# MP135_11x11.net
KiCad netlist of a schematic drawn in Altium Designer
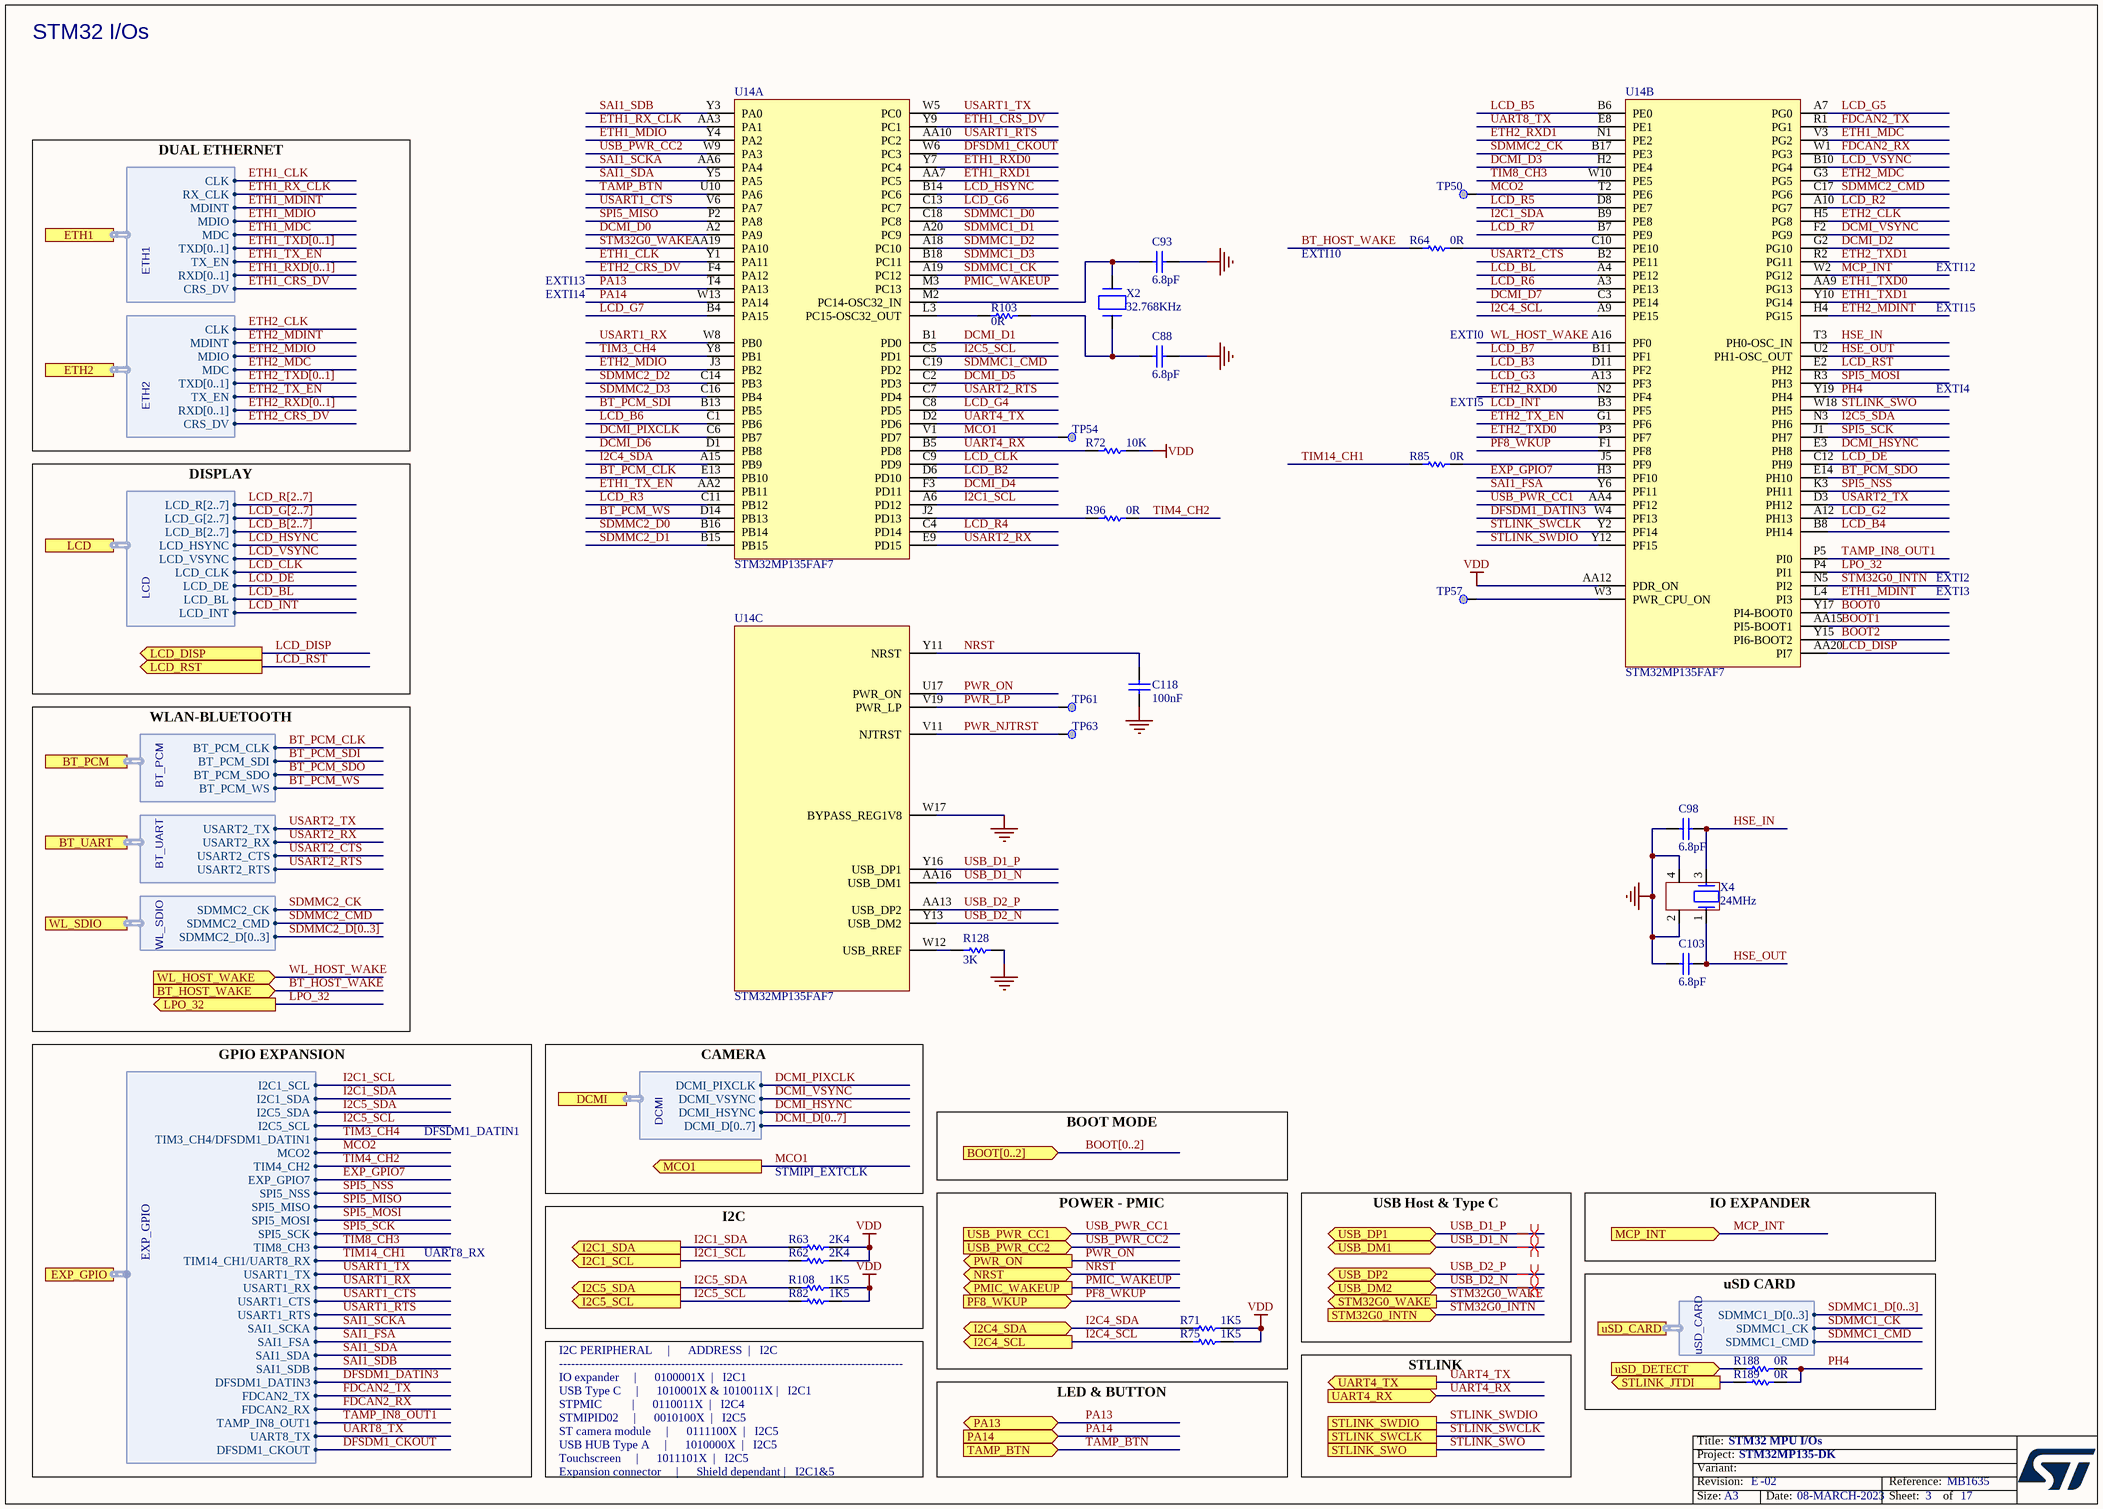
[diagram p0: MP135_11x11.SchDoc]

(export (version "E")
  (design (tool "Eeschema 10.0.6"))
  (components
    (comp (ref "C88")
      (value "6.8pF")
      (footprint "C0402")
      (description "Capacitor, MLCC, 6.8pF, 50V, NPO, +/-0.25pF, 0402, T=0.5mm")
      (fields
        (field (name "INTERNAL_PART_NUMBER") "MCD-00674")
        (field (name "MANUFACTURER_PART_NUMBER") "CC0402CRNPO9BN6R8")
      )
      (libsource (lib "MCD_PARTS_database") (part "Capacitor"))
    )
    (comp (ref "C93")
      (value "6.8pF")
      (footprint "C0402")
      (description "Capacitor, MLCC, 6.8pF, 50V, NPO, +/-0.25pF, 0402, T=0.5mm")
      (fields
        (field (name "INTERNAL_PART_NUMBER") "MCD-00674")
        (field (name "MANUFACTURER_PART_NUMBER") "CC0402CRNPO9BN6R8")
      )
      (libsource (lib "MCD_PARTS_database") (part "Capacitor"))
    )
    (comp (ref "C98")
      (value "6.8pF")
      (footprint "C0402")
      (description "Capacitor, MLCC, 6.8pF, 50V, NPO, +/-0.25pF, 0402, T=0.5mm")
      (fields
        (field (name "INTERNAL_PART_NUMBER") "MCD-00674")
        (field (name "MANUFACTURER_PART_NUMBER") "CC0402CRNPO9BN6R8")
      )
      (libsource (lib "MCD_PARTS_database") (part "Capacitor"))
    )
    (comp (ref "C103")
      (value "6.8pF")
      (footprint "C0402")
      (description "Capacitor, MLCC, 6.8pF, 50V, NPO, +/-0.25pF, 0402, T=0.5mm")
      (fields
        (field (name "INTERNAL_PART_NUMBER") "MCD-00674")
        (field (name "MANUFACTURER_PART_NUMBER") "CC0402CRNPO9BN6R8")
      )
      (libsource (lib "MCD_PARTS_database") (part "Capacitor"))
    )
    (comp (ref "C118")
      (value "100nF")
      (footprint "C0402")
      (description "Capacitor, MLCC, 100nF, 16V, X7R, +/-10%, 0402, T=0.5mm")
      (fields
        (field (name "INTERNAL_PART_NUMBER") "MCD-00006")
        (field (name "MANUFACTURER_PART_NUMBER") "CC0402KRX7R7BB104")
      )
      (libsource (lib "MCD_PARTS_database") (part "Capacitor"))
    )
    (comp (ref "R62")
      (value "2K4")
      (footprint "R0402")
      (description "Resistor, 2K4, 0402, +/-1%, 1/16W")
      (fields (field (name "INTERNAL_PART_NUMBER") "MCD-00433") (field (name "MANUFACTURER") "YAGEO"))
      (libsource (lib "MCD_PARTS_database") (part "Resistor"))
    )
    (comp (ref "R63")
      (value "2K4")
      (footprint "R0402")
      (description "Resistor, 2K4, 0402, +/-1%, 1/16W")
      (fields (field (name "INTERNAL_PART_NUMBER") "MCD-00433") (field (name "MANUFACTURER") "YAGEO"))
      (libsource (lib "MCD_PARTS_database") (part "Resistor"))
    )
    (comp (ref "R64")
      (value "0R")
      (footprint "R0402")
      (description "Resistor, 0R, 0402, +/-5%, 1/16W")
      (fields (field (name "INTERNAL_PART_NUMBER") "MCD-00052") (field (name "MANUFACTURER") "YAGEO"))
      (libsource (lib "MCD_PARTS_database") (part "Resistor"))
    )
    (comp (ref "R71")
      (value "1K5")
      (footprint "R0402")
      (description "Resistor, 1K5, 0402, +/-1%, 1/16W")
      (fields (field (name "INTERNAL_PART_NUMBER") "MCD-00068") (field (name "MANUFACTURER") "YAGEO"))
      (libsource (lib "MCD_PARTS_database") (part "Resistor"))
    )
    (comp (ref "R72")
      (value "10K")
      (footprint "R0402")
      (description "Resistor, 10K, 0402, +/-1%, 1/16W")
      (fields
        (field (name "INTERNAL_PART_NUMBER") "MCD-00053")
        (field (name "MANUFACTURER_PART_NUMBER") "RC0402FR-0710KL")
      )
      (libsource (lib "MCD_PARTS_database") (part "Resistor"))
    )
    (comp (ref "R75")
      (value "1K5")
      (footprint "R0402")
      (description "Resistor, 1K5, 0402, +/-1%, 1/16W")
      (fields (field (name "INTERNAL_PART_NUMBER") "MCD-00068") (field (name "MANUFACTURER") "YAGEO"))
      (libsource (lib "MCD_PARTS_database") (part "Resistor"))
    )
    (comp (ref "R82")
      (value "1K5")
      (footprint "R0402")
      (description "Resistor, 1K5, 0402, +/-1%, 1/16W")
      (fields (field (name "INTERNAL_PART_NUMBER") "MCD-00068") (field (name "MANUFACTURER") "YAGEO"))
      (libsource (lib "MCD_PARTS_database") (part "Resistor"))
    )
    (comp (ref "R85")
      (value "0R")
      (footprint "R0402")
      (description "Resistor, 0R, 0402, +/-5%, 1/16W")
      (fields (field (name "INTERNAL_PART_NUMBER") "MCD-00052") (field (name "MANUFACTURER") "YAGEO"))
      (libsource (lib "MCD_PARTS_database") (part "Resistor"))
    )
    (comp (ref "R96")
      (value "0R")
      (footprint "R0402")
      (description "Resistor, 0R, 0402, +/-5%, 1/16W")
      (fields (field (name "INTERNAL_PART_NUMBER") "MCD-00052") (field (name "MANUFACTURER") "YAGEO"))
      (libsource (lib "MCD_PARTS_database") (part "Resistor"))
    )
    (comp (ref "R103")
      (value "0R")
      (footprint "R0402")
      (description "Resistor, 0R, 0402, +/-5%, 1/16W")
      (fields
        (field (name "INTERNAL_PART_NUMBER") "MCD-00052")
        (field (name "MANUFACTURER_PART_NUMBER") "RC0402JR-070RL")
      )
      (libsource (lib "MCD_PARTS_database") (part "Resistor"))
    )
    (comp (ref "R108")
      (value "1K5")
      (footprint "R0402")
      (description "Resistor, 1K5, 0402, +/-1%, 1/16W")
      (fields (field (name "INTERNAL_PART_NUMBER") "MCD-00068") (field (name "MANUFACTURER") "YAGEO"))
      (libsource (lib "MCD_PARTS_database") (part "Resistor"))
    )
    (comp (ref "R128")
      (value "3K")
      (footprint "R0402")
      (description "Resistor, 3K, 0402, +/-1%, 1/16W")
      (fields (field (name "INTERNAL_PART_NUMBER") "MCD-00185") (field (name "MANUFACTURER") "YAGEO"))
      (libsource (lib "MCD_PARTS_database") (part "Resistor"))
    )
    (comp (ref "R188")
      (value "0R")
      (footprint "R0402")
      (description "Resistor, 0R, 0402, +/-5%, 1/16W")
      (fields (field (name "INTERNAL_PART_NUMBER") "MCD-00052") (field (name "MANUFACTURER") "YAGEO"))
      (libsource (lib "MCD_PARTS_database") (part "Resistor"))
    )
    (comp (ref "R189")
      (value "0R")
      (footprint "R0402")
      (description "Resistor, 0R, 0402, +/-5%, 1/16W")
      (fields (field (name "INTERNAL_PART_NUMBER") "MCD-00052") (field (name "MANUFACTURER") "YAGEO"))
      (libsource (lib "MCD_PARTS_database") (part "Resistor"))
    )
    (comp (ref "TP50")
      (value "Test Point")
      (footprint "TP_SMD_1MM")
      (description "Test Point 1mm")
      (fields (field (name "INTERNAL_PART_NUMBER") "MCD-00074"))
      (libsource (lib "") (part "Test Point_1"))
    )
    (comp (ref "TP54")
      (value "Test Point")
      (footprint "TP_SMD_1MM")
      (description "Test Point 1mm")
      (fields (field (name "INTERNAL_PART_NUMBER") "MCD-00074"))
      (libsource (lib "MCD_PARTS_database") (part "Test Point"))
    )
    (comp (ref "TP57")
      (value "Test Point")
      (footprint "TP_SMD_1MM")
      (description "Test Point 1mm")
      (fields (field (name "INTERNAL_PART_NUMBER") "MCD-00074"))
      (libsource (lib "") (part "Test Point_1"))
    )
    (comp (ref "TP61")
      (value "Test Point")
      (footprint "TP_SMD_1MM")
      (description "Test Point 1mm")
      (fields (field (name "INTERNAL_PART_NUMBER") "MCD-00074"))
      (libsource (lib "MCD_PARTS_database") (part "Test Point"))
    )
    (comp (ref "TP63")
      (value "Test Point")
      (footprint "TP_SMD_1MM")
      (description "Test Point 1mm")
      (fields (field (name "INTERNAL_PART_NUMBER") "MCD-00074"))
      (libsource (lib "MCD_PARTS_database") (part "Test Point"))
    )
    (comp (ref "U14")
      (value "STM32MP135FAF7")
      (footprint "ICC_TFBGA320_11X11_STM32MP135FA7_P050_H1P20")
      (fields
        (field (name "INTERNAL_PART_NUMBER") "MCD-02251")
        (field (name "MANUFACTURER") "STMICROELECTRONICS")
      )
      (libsource (lib "MCD_PARTS_database") (part "STM32MP135FAF7"))
    )
    (comp (ref "X2")
      (value "32.768KHz")
      (footprint "CRY_NX2012SA_2P")
      (description "Crystal, 32.768kHz, 6pF, +/-20ppm, 80K, 2.05x1.2mm")
      (fields
        (field (name "INTERNAL_PART_NUMBER") "MCD-01479")
        (field (name "MANUFACTURER_PART_NUMBER") "NX2012SA-32.768KHZ-EXS00A-MU00527")
      )
      (libsource (lib "MCD_PARTS_database") (part "XTAL_2_PINS"))
    )
    (comp (ref "X4")
      (value "24MHz")
      (footprint "CRY_NX2016SA_4P")
      (description "Crystal, 24MHz, 6pF, +/-20ppm, 80R, 2x1.6mm")
      (fields (field (name "INTERNAL_PART_NUMBER") "MCD-01036") (field (name "BMS_PART_NUMBER") "9157045"))
      (libsource (lib "MCD_PARTS_database") (part "XTAL_4_PINS"))
    )
  )
  (nets
    (net (code "10") (name "/BOOT0") (class "Default")
      (node (ref "U14") (pin "Y17") (pinfunction "PI4-BOOT0_Y17") (pintype "passive"))
    )
    (net (code "11") (name "/BOOT1") (class "Default")
      (node (ref "U14") (pin "AA15") (pinfunction "PI5-BOOT1_AA15") (pintype "passive"))
    )
    (net (code "12") (name "/BOOT2") (class "Default")
      (node (ref "U14") (pin "Y15") (pinfunction "PI6-BOOT2_Y15") (pintype "passive"))
    )
    (net (code "14") (name "/BT_HOST_WAKE") (class "Default")
      (node (ref "R64") (pin "1") (pinfunction "1_1") (pintype "passive"))
    )
    (net (code "15") (name "/BT_PCM_CLK") (class "Default")
      (node (ref "U14") (pin "E13") (pinfunction "PB10_E13") (pintype "passive"))
    )
    (net (code "16") (name "/BT_PCM_SDI") (class "Default")
      (node (ref "U14") (pin "B13") (pinfunction "PB5_B13") (pintype "passive"))
    )
    (net (code "17") (name "/BT_PCM_SDO") (class "Default")
      (node (ref "U14") (pin "E14") (pinfunction "PH10_E14") (pintype "passive"))
    )
    (net (code "18") (name "/BT_PCM_WS") (class "Default")
      (node (ref "U14") (pin "D14") (pinfunction "PB13_D14") (pintype "passive"))
    )
    (net (code "19") (name "/DCMI_D0") (class "Default")
      (node (ref "U14") (pin "A2") (pinfunction "PA9_A2") (pintype "passive"))
    )
    (net (code "20") (name "/DCMI_D1") (class "Default")
      (node (ref "U14") (pin "B1") (pinfunction "PD0_B1") (pintype "passive"))
    )
    (net (code "21") (name "/DCMI_D2") (class "Default")
      (node (ref "U14") (pin "G2") (pinfunction "PG10_G2") (pintype "passive"))
    )
    (net (code "22") (name "/DCMI_D3") (class "Default")
      (node (ref "U14") (pin "H2") (pinfunction "PE4_H2") (pintype "passive"))
    )
    (net (code "23") (name "/DCMI_D4") (class "Default")
      (node (ref "U14") (pin "F3") (pinfunction "PD11_F3") (pintype "passive"))
    )
    (net (code "24") (name "/DCMI_D5") (class "Default")
      (node (ref "U14") (pin "C2") (pinfunction "PD3_C2") (pintype "passive"))
    )
    (net (code "25") (name "/DCMI_D6") (class "Default")
      (node (ref "U14") (pin "D1") (pinfunction "PB8_D1") (pintype "passive"))
    )
    (net (code "26") (name "/DCMI_D7") (class "Default")
      (node (ref "U14") (pin "C3") (pinfunction "PE14_C3") (pintype "passive"))
    )
    (net (code "27") (name "/DCMI_HSYNC") (class "Default")
      (node (ref "U14") (pin "E3") (pinfunction "PH8_E3") (pintype "passive"))
    )
    (net (code "28") (name "/DCMI_PIXCLK") (class "Default")
      (node (ref "U14") (pin "C6") (pinfunction "PB7_C6") (pintype "passive"))
    )
    (net (code "29") (name "/DCMI_VSYNC") (class "Default")
      (node (ref "U14") (pin "F2") (pinfunction "PG9_F2") (pintype "passive"))
    )
    (net (code "31") (name "/DFSDM1_CKOUT") (class "Default")
      (node (ref "U14") (pin "W6") (pinfunction "PC3_W6") (pintype "passive"))
    )
    (net (code "32") (name "/DFSDM1_DATIN3") (class "Default")
      (node (ref "U14") (pin "W4") (pinfunction "PF13_W4") (pintype "passive"))
    )
    (net (code "33") (name "/ETH1_CLK") (class "Default")
      (node (ref "U14") (pin "Y1") (pinfunction "PA11_Y1") (pintype "passive"))
    )
    (net (code "34") (name "/ETH1_CRS_DV") (class "Default")
      (node (ref "U14") (pin "Y9") (pinfunction "PC1_Y9") (pintype "passive"))
    )
    (net (code "35") (name "/ETH1_MDC") (class "Default")
      (node (ref "U14") (pin "V3") (pinfunction "PG2_V3") (pintype "passive"))
    )
    (net (code "36") (name "/ETH1_MDINT") (class "Default")
      (node (ref "U14") (pin "L4") (pinfunction "PI3_L4") (pintype "passive"))
    )
    (net (code "37") (name "/ETH1_MDIO") (class "Default")
      (node (ref "U14") (pin "Y4") (pinfunction "PA2_Y4") (pintype "passive"))
    )
    (net (code "38") (name "/ETH1_RXD0") (class "Default")
      (node (ref "U14") (pin "Y7") (pinfunction "PC4_Y7") (pintype "passive"))
    )
    (net (code "39") (name "/ETH1_RXD1") (class "Default")
      (node (ref "U14") (pin "AA7") (pinfunction "PC5_AA7") (pintype "passive"))
    )
    (net (code "40") (name "/ETH1_RX_CLK") (class "Default")
      (node (ref "U14") (pin "AA3") (pinfunction "PA1_AA3") (pintype "passive"))
    )
    (net (code "41") (name "/ETH1_TXD0") (class "Default")
      (node (ref "U14") (pin "AA9") (pinfunction "PG13_AA9") (pintype "passive"))
    )
    (net (code "42") (name "/ETH1_TXD1") (class "Default")
      (node (ref "U14") (pin "Y10") (pinfunction "PG14_Y10") (pintype "passive"))
    )
    (net (code "44") (name "/ETH1_TX_EN") (class "Default")
      (node (ref "U14") (pin "AA2") (pinfunction "PB11_AA2") (pintype "passive"))
    )
    (net (code "46") (name "/ETH2_CLK") (class "Default")
      (node (ref "U14") (pin "H5") (pinfunction "PG8_H5") (pintype "passive"))
    )
    (net (code "47") (name "/ETH2_CRS_DV") (class "Default")
      (node (ref "U14") (pin "F4") (pinfunction "PA12_F4") (pintype "passive"))
    )
    (net (code "48") (name "/ETH2_MDC") (class "Default")
      (node (ref "U14") (pin "G3") (pinfunction "PG5_G3") (pintype "passive"))
    )
    (net (code "49") (name "/ETH2_MDINT") (class "Default")
      (node (ref "U14") (pin "H4") (pinfunction "PG15_H4") (pintype "passive"))
    )
    (net (code "50") (name "/ETH2_MDIO") (class "Default")
      (node (ref "U14") (pin "J3") (pinfunction "PB2_J3") (pintype "passive"))
    )
    (net (code "51") (name "/ETH2_RXD0") (class "Default")
      (node (ref "U14") (pin "N2") (pinfunction "PF4_N2") (pintype "passive"))
    )
    (net (code "52") (name "/ETH2_RXD1") (class "Default")
      (node (ref "U14") (pin "N1") (pinfunction "PE2_N1") (pintype "passive"))
    )
    (net (code "54") (name "/ETH2_TXD0") (class "Default")
      (node (ref "U14") (pin "P3") (pinfunction "PF7_P3") (pintype "passive"))
    )
    (net (code "55") (name "/ETH2_TXD1") (class "Default")
      (node (ref "U14") (pin "R2") (pinfunction "PG11_R2") (pintype "passive"))
    )
    (net (code "57") (name "/ETH2_TX_EN") (class "Default")
      (node (ref "U14") (pin "G1") (pinfunction "PF6_G1") (pintype "passive"))
    )
    (net (code "58") (name "/EXP_GPIO7") (class "Default")
      (node (ref "U14") (pin "H3") (pinfunction "PF10_H3") (pintype "passive"))
    )
    (net (code "59") (name "/FDCAN2_RX") (class "Default")
      (node (ref "U14") (pin "W1") (pinfunction "PG3_W1") (pintype "passive"))
    )
    (net (code "60") (name "/FDCAN2_TX") (class "Default")
      (node (ref "U14") (pin "R1") (pinfunction "PG1_R1") (pintype "passive"))
    )
    (net (code "61") (name "/HSE_IN") (class "Default")
      (node (ref "C98") (pin "2") (pinfunction "2_2") (pintype "passive"))
      (node (ref "U14") (pin "T3") (pinfunction "PH0-OSC_IN_T3") (pintype "passive"))
      (node (ref "X4") (pin "3") (pinfunction "3_3") (pintype "passive"))
    )
    (net (code "62") (name "/HSE_OUT") (class "Default")
      (node (ref "C103") (pin "1") (pinfunction "1_1") (pintype "passive"))
      (node (ref "U14") (pin "U2") (pinfunction "PH1-OSC_OUT_U2") (pintype "passive"))
      (node (ref "X4") (pin "1") (pinfunction "1_1") (pintype "passive"))
    )
    (net (code "63") (name "/I2C1_SCL") (class "Default")
      (node (ref "R62") (pin "1") (pinfunction "1_1") (pintype "passive"))
      (node (ref "U14") (pin "A6") (pinfunction "PD12_A6") (pintype "passive"))
    )
    (net (code "64") (name "/I2C1_SDA") (class "Default")
      (node (ref "R63") (pin "1") (pinfunction "1_1") (pintype "passive"))
      (node (ref "U14") (pin "B9") (pinfunction "PE8_B9") (pintype "passive"))
    )
    (net (code "65") (name "/I2C4_SCL") (class "Default")
      (node (ref "R75") (pin "1") (pinfunction "1_1") (pintype "passive"))
      (node (ref "U14") (pin "A9") (pinfunction "PE15_A9") (pintype "passive"))
    )
    (net (code "66") (name "/I2C4_SDA") (class "Default")
      (node (ref "R71") (pin "1") (pinfunction "1_1") (pintype "passive"))
      (node (ref "U14") (pin "A15") (pinfunction "PB9_A15") (pintype "passive"))
    )
    (net (code "67") (name "/I2C5_SCL") (class "Default")
      (node (ref "R82") (pin "1") (pinfunction "1_1") (pintype "passive"))
      (node (ref "U14") (pin "C5") (pinfunction "PD1_C5") (pintype "passive"))
    )
    (net (code "68") (name "/I2C5_SDA") (class "Default")
      (node (ref "R108") (pin "1") (pinfunction "1_1") (pintype "passive"))
      (node (ref "U14") (pin "N3") (pinfunction "PH6_N3") (pintype "passive"))
    )
    (net (code "69") (name "/LCD_B2") (class "Default")
      (node (ref "U14") (pin "D6") (pinfunction "PD10_D6") (pintype "passive"))
    )
    (net (code "70") (name "/LCD_B3") (class "Default")
      (node (ref "U14") (pin "D11") (pinfunction "PF2_D11") (pintype "passive"))
    )
    (net (code "71") (name "/LCD_B4") (class "Default")
      (node (ref "U14") (pin "B8") (pinfunction "PH14_B8") (pintype "passive"))
    )
    (net (code "72") (name "/LCD_B5") (class "Default")
      (node (ref "U14") (pin "B6") (pinfunction "PE0_B6") (pintype "passive"))
    )
    (net (code "73") (name "/LCD_B6") (class "Default")
      (node (ref "U14") (pin "C1") (pinfunction "PB6_C1") (pintype "passive"))
    )
    (net (code "74") (name "/LCD_B7") (class "Default")
      (node (ref "U14") (pin "B11") (pinfunction "PF1_B11") (pintype "passive"))
    )
    (net (code "75") (name "/LCD_BL") (class "Default")
      (node (ref "U14") (pin "A4") (pinfunction "PE12_A4") (pintype "passive"))
    )
    (net (code "76") (name "/LCD_CLK") (class "Default")
      (node (ref "U14") (pin "C9") (pinfunction "PD9_C9") (pintype "passive"))
    )
    (net (code "77") (name "/LCD_DE") (class "Default")
      (node (ref "U14") (pin "C12") (pinfunction "PH9_C12") (pintype "passive"))
    )
    (net (code "78") (name "/LCD_DISP") (class "Default")
      (node (ref "U14") (pin "AA20") (pinfunction "PI7_AA20") (pintype "passive"))
    )
    (net (code "79") (name "/LCD_G2") (class "Default")
      (node (ref "U14") (pin "A12") (pinfunction "PH13_A12") (pintype "passive"))
    )
    (net (code "80") (name "/LCD_G3") (class "Default")
      (node (ref "U14") (pin "A13") (pinfunction "PF3_A13") (pintype "passive"))
    )
    (net (code "81") (name "/LCD_G4") (class "Default")
      (node (ref "U14") (pin "C8") (pinfunction "PD5_C8") (pintype "passive"))
    )
    (net (code "82") (name "/LCD_G5") (class "Default")
      (node (ref "U14") (pin "A7") (pinfunction "PG0_A7") (pintype "passive"))
    )
    (net (code "83") (name "/LCD_G6") (class "Default")
      (node (ref "U14") (pin "C13") (pinfunction "PC7_C13") (pintype "passive"))
    )
    (net (code "84") (name "/LCD_G7") (class "Default")
      (node (ref "U14") (pin "B4") (pinfunction "PA15_B4") (pintype "passive"))
    )
    (net (code "86") (name "/LCD_HSYNC") (class "Default")
      (node (ref "U14") (pin "B14") (pinfunction "PC6_B14") (pintype "passive"))
    )
    (net (code "87") (name "/LCD_INT") (class "Default")
      (node (ref "U14") (pin "B3") (pinfunction "PF5_B3") (pintype "passive"))
    )
    (net (code "88") (name "/LCD_R2") (class "Default")
      (node (ref "U14") (pin "A10") (pinfunction "PG7_A10") (pintype "passive"))
    )
    (net (code "89") (name "/LCD_R3") (class "Default")
      (node (ref "U14") (pin "C11") (pinfunction "PB12_C11") (pintype "passive"))
    )
    (net (code "90") (name "/LCD_R4") (class "Default")
      (node (ref "U14") (pin "C4") (pinfunction "PD14_C4") (pintype "passive"))
    )
    (net (code "91") (name "/LCD_R5") (class "Default")
      (node (ref "U14") (pin "D8") (pinfunction "PE7_D8") (pintype "passive"))
    )
    (net (code "92") (name "/LCD_R6") (class "Default")
      (node (ref "U14") (pin "A3") (pinfunction "PE13_A3") (pintype "passive"))
    )
    (net (code "93") (name "/LCD_R7") (class "Default")
      (node (ref "U14") (pin "B7") (pinfunction "PE9_B7") (pintype "passive"))
    )
    (net (code "94") (name "/LCD_RST") (class "Default")
      (node (ref "U14") (pin "E2") (pinfunction "PH2_E2") (pintype "passive"))
    )
    (net (code "96") (name "/LCD_VSYNC") (class "Default")
      (node (ref "U14") (pin "B10") (pinfunction "PG4_B10") (pintype "passive"))
    )
    (net (code "98") (name "/LPO_32") (class "Default")
      (node (ref "U14") (pin "P4") (pinfunction "PI1_P4") (pintype "passive"))
    )
    (net (code "99") (name "/MCO1") (class "Default")
      (node (ref "TP54") (pin "1") (pinfunction "1_1") (pintype "passive"))
      (node (ref "U14") (pin "V1") (pinfunction "PD7_V1") (pintype "passive"))
    )
    (net (code "100") (name "/MCO2") (class "Default")
      (node (ref "TP50") (pin "1") (pinfunction "1_1") (pintype "passive"))
      (node (ref "U14") (pin "T2") (pinfunction "PE6_T2") (pintype "passive"))
    )
    (net (code "101") (name "/MCP_INT") (class "Default")
      (node (ref "U14") (pin "W2") (pinfunction "PG12_W2") (pintype "passive"))
    )
    (net (code "102") (name "/NRST") (class "Default")
      (node (ref "C118") (pin "1") (pinfunction "1_1") (pintype "passive"))
      (node (ref "U14") (pin "Y11") (pinfunction "NRST_Y11") (pintype "passive"))
    )
    (net (code "103") (name "/PA13") (class "Default")
      (node (ref "U14") (pin "T4") (pinfunction "PA13_T4") (pintype "passive"))
    )
    (net (code "104") (name "/PA14") (class "Default")
      (node (ref "U14") (pin "W13") (pinfunction "PA14_W13") (pintype "passive"))
    )
    (net (code "105") (name "/PF8_WKUP") (class "Default")
      (node (ref "U14") (pin "F1") (pinfunction "PF8_F1") (pintype "passive"))
    )
    (net (code "106") (name "/PH4") (class "Default")
      (node (ref "R188") (pin "2") (pinfunction "2_2") (pintype "passive"))
      (node (ref "R189") (pin "2") (pinfunction "2_2") (pintype "passive"))
      (node (ref "U14") (pin "Y19") (pinfunction "PH4_Y19") (pintype "passive"))
    )
    (net (code "107") (name "/PMIC_WAKEUP") (class "Default")
      (node (ref "U14") (pin "M3") (pinfunction "PC13_M3") (pintype "passive"))
    )
    (net (code "108") (name "/PWR_LP") (class "Default")
      (node (ref "TP61") (pin "1") (pinfunction "1_1") (pintype "passive"))
      (node (ref "U14") (pin "V19") (pinfunction "PWR_LP_V19") (pintype "passive"))
    )
    (net (code "109") (name "/PWR_NJTRST") (class "Default")
      (node (ref "TP63") (pin "1") (pinfunction "1_1") (pintype "passive"))
      (node (ref "U14") (pin "V11") (pinfunction "NJTRST_V11") (pintype "passive"))
    )
    (net (code "110") (name "/PWR_ON") (class "Default")
      (node (ref "U14") (pin "U17") (pinfunction "PWR_ON_U17") (pintype "passive"))
    )
    (net (code "111") (name "/SAI1_FSA") (class "Default")
      (node (ref "U14") (pin "Y6") (pinfunction "PF11_Y6") (pintype "passive"))
    )
    (net (code "112") (name "/SAI1_SCKA") (class "Default")
      (node (ref "U14") (pin "AA6") (pinfunction "PA4_AA6") (pintype "passive"))
    )
    (net (code "113") (name "/SAI1_SDA") (class "Default")
      (node (ref "U14") (pin "Y5") (pinfunction "PA5_Y5") (pintype "passive"))
    )
    (net (code "114") (name "/SAI1_SDB") (class "Default")
      (node (ref "U14") (pin "Y3") (pinfunction "PA0_Y3") (pintype "passive"))
    )
    (net (code "115") (name "/SDMMC1_CK") (class "Default")
      (node (ref "U14") (pin "A19") (pinfunction "PC12_A19") (pintype "passive"))
    )
    (net (code "116") (name "/SDMMC1_CMD") (class "Default")
      (node (ref "U14") (pin "C19") (pinfunction "PD2_C19") (pintype "passive"))
    )
    (net (code "117") (name "/SDMMC1_D0") (class "Default")
      (node (ref "U14") (pin "C18") (pinfunction "PC8_C18") (pintype "passive"))
    )
    (net (code "118") (name "/SDMMC1_D1") (class "Default")
      (node (ref "U14") (pin "A20") (pinfunction "PC9_A20") (pintype "passive"))
    )
    (net (code "119") (name "/SDMMC1_D2") (class "Default")
      (node (ref "U14") (pin "A18") (pinfunction "PC10_A18") (pintype "passive"))
    )
    (net (code "120") (name "/SDMMC1_D3") (class "Default")
      (node (ref "U14") (pin "B18") (pinfunction "PC11_B18") (pintype "passive"))
    )
    (net (code "122") (name "/SDMMC2_CK") (class "Default")
      (node (ref "U14") (pin "B17") (pinfunction "PE3_B17") (pintype "passive"))
    )
    (net (code "123") (name "/SDMMC2_CMD") (class "Default")
      (node (ref "U14") (pin "C17") (pinfunction "PG6_C17") (pintype "passive"))
    )
    (net (code "124") (name "/SDMMC2_D0") (class "Default")
      (node (ref "U14") (pin "B16") (pinfunction "PB14_B16") (pintype "passive"))
    )
    (net (code "125") (name "/SDMMC2_D1") (class "Default")
      (node (ref "U14") (pin "B15") (pinfunction "PB15_B15") (pintype "passive"))
    )
    (net (code "126") (name "/SDMMC2_D2") (class "Default")
      (node (ref "U14") (pin "C14") (pinfunction "PB3_C14") (pintype "passive"))
    )
    (net (code "127") (name "/SDMMC2_D3") (class "Default")
      (node (ref "U14") (pin "C16") (pinfunction "PB4_C16") (pintype "passive"))
    )
    (net (code "128") (name "/SPI5_MISO") (class "Default")
      (node (ref "U14") (pin "P2") (pinfunction "PA8_P2") (pintype "passive"))
    )
    (net (code "129") (name "/SPI5_MOSI") (class "Default")
      (node (ref "U14") (pin "R3") (pinfunction "PH3_R3") (pintype "passive"))
    )
    (net (code "130") (name "/SPI5_NSS") (class "Default")
      (node (ref "U14") (pin "K3") (pinfunction "PH11_K3") (pintype "passive"))
    )
    (net (code "131") (name "/SPI5_SCK") (class "Default")
      (node (ref "U14") (pin "J1") (pinfunction "PH7_J1") (pintype "passive"))
    )
    (net (code "132") (name "/STLINK_JTDI") (class "Default")
      (node (ref "R189") (pin "1") (pinfunction "1_1") (pintype "passive"))
    )
    (net (code "133") (name "/STLINK_SWCLK") (class "Default")
      (node (ref "U14") (pin "Y2") (pinfunction "PF14_Y2") (pintype "passive"))
    )
    (net (code "134") (name "/STLINK_SWDIO") (class "Default")
      (node (ref "U14") (pin "Y12") (pinfunction "PF15_Y12") (pintype "passive"))
    )
    (net (code "135") (name "/STLINK_SWO") (class "Default")
      (node (ref "U14") (pin "W18") (pinfunction "PH5_W18") (pintype "passive"))
    )
    (net (code "136") (name "/STM32G0_INTN") (class "Default")
      (node (ref "U14") (pin "N5") (pinfunction "PI2_N5") (pintype "passive"))
    )
    (net (code "137") (name "/STM32G0_WAKE") (class "Default")
      (node (ref "U14") (pin "AA19") (pinfunction "PA10_AA19") (pintype "passive"))
    )
    (net (code "138") (name "/TAMP_BTN") (class "Default")
      (node (ref "U14") (pin "U10") (pinfunction "PA6_U10") (pintype "passive"))
    )
    (net (code "139") (name "/TAMP_IN8_OUT1") (class "Default")
      (node (ref "U14") (pin "P5") (pinfunction "PI0_P5") (pintype "passive"))
    )
    (net (code "140") (name "/TIM3_CH4") (class "Default")
      (node (ref "U14") (pin "Y8") (pinfunction "PB1_Y8") (pintype "passive"))
    )
    (net (code "141") (name "/TIM4_CH2") (class "Default")
      (node (ref "R96") (pin "2") (pinfunction "2_2") (pintype "passive"))
    )
    (net (code "142") (name "/TIM8_CH3") (class "Default")
      (node (ref "U14") (pin "W10") (pinfunction "PE5_W10") (pintype "passive"))
    )
    (net (code "143") (name "/TIM14_CH1") (class "Default")
      (node (ref "R85") (pin "1") (pinfunction "1_1") (pintype "passive"))
    )
    (net (code "144") (name "/UART4_RX") (class "Default")
      (node (ref "R72") (pin "1") (pinfunction "1_1") (pintype "passive"))
      (node (ref "U14") (pin "B5") (pinfunction "PD8_B5") (pintype "passive"))
    )
    (net (code "145") (name "/UART4_TX") (class "Default")
      (node (ref "U14") (pin "D2") (pinfunction "PD6_D2") (pintype "passive"))
    )
    (net (code "146") (name "/UART8_TX") (class "Default")
      (node (ref "U14") (pin "E8") (pinfunction "PE1_E8") (pintype "passive"))
    )
    (net (code "147") (name "/USART1_CTS") (class "Default")
      (node (ref "U14") (pin "V6") (pinfunction "PA7_V6") (pintype "passive"))
    )
    (net (code "148") (name "/USART1_RTS") (class "Default")
      (node (ref "U14") (pin "AA10") (pinfunction "PC2_AA10") (pintype "passive"))
    )
    (net (code "149") (name "/USART1_RX") (class "Default")
      (node (ref "U14") (pin "W8") (pinfunction "PB0_W8") (pintype "passive"))
    )
    (net (code "150") (name "/USART1_TX") (class "Default")
      (node (ref "U14") (pin "W5") (pinfunction "PC0_W5") (pintype "passive"))
    )
    (net (code "151") (name "/USART2_CTS") (class "Default")
      (node (ref "U14") (pin "B2") (pinfunction "PE11_B2") (pintype "passive"))
    )
    (net (code "152") (name "/USART2_RTS") (class "Default")
      (node (ref "U14") (pin "C7") (pinfunction "PD4_C7") (pintype "passive"))
    )
    (net (code "153") (name "/USART2_RX") (class "Default")
      (node (ref "U14") (pin "E9") (pinfunction "PD15_E9") (pintype "passive"))
    )
    (net (code "154") (name "/USART2_TX") (class "Default")
      (node (ref "U14") (pin "D3") (pinfunction "PH12_D3") (pintype "passive"))
    )
    (net (code "155") (name "/USB_D1_N") (class "Default")
      (node (ref "U14") (pin "AA16") (pinfunction "USB_DM1_AA16") (pintype "passive"))
    )
    (net (code "156") (name "/USB_D1_P") (class "Default")
      (node (ref "U14") (pin "Y16") (pinfunction "USB_DP1_Y16") (pintype "passive"))
    )
    (net (code "157") (name "/USB_D2_N") (class "Default")
      (node (ref "U14") (pin "Y13") (pinfunction "USB_DM2_Y13") (pintype "passive"))
    )
    (net (code "158") (name "/USB_D2_P") (class "Default")
      (node (ref "U14") (pin "AA13") (pinfunction "USB_DP2_AA13") (pintype "passive"))
    )
    (net (code "159") (name "/USB_PWR_CC1") (class "Default")
      (node (ref "U14") (pin "AA4") (pinfunction "PF12_AA4") (pintype "passive"))
    )
    (net (code "160") (name "/USB_PWR_CC2") (class "Default")
      (node (ref "U14") (pin "W9") (pinfunction "PA3_W9") (pintype "passive"))
    )
    (net (code "161") (name "/WL_HOST_WAKE") (class "Default")
      (node (ref "U14") (pin "A16") (pinfunction "PF0_A16") (pintype "passive"))
    )
    (net (code "163") (name "/uSD_DETECT") (class "Default")
      (node (ref "R188") (pin "1") (pinfunction "1_1") (pintype "passive"))
    )
    (net (code "173") (name "GND") (class "Default")
      (node (ref "C103") (pin "2") (pinfunction "2_2") (pintype "passive"))
      (node (ref "C118") (pin "2") (pinfunction "2_2") (pintype "passive"))
      (node (ref "C88") (pin "2") (pinfunction "2_2") (pintype "passive"))
      (node (ref "C93") (pin "2") (pinfunction "2_2") (pintype "passive"))
      (node (ref "C98") (pin "1") (pinfunction "1_1") (pintype "passive"))
      (node (ref "R128") (pin "2") (pinfunction "2_2") (pintype "passive"))
      (node (ref "U14") (pin "W17") (pinfunction "BYPASS_REG1V8_W17") (pintype "passive"))
      (node (ref "X4") (pin "2") (pinfunction "2_2") (pintype "passive"))
      (node (ref "X4") (pin "4") (pinfunction "4_4") (pintype "passive"))
    )
    (net (code "174") (name "Net-(U14A-PC14-OSC32_IN)") (class "Default")
      (node (ref "C93") (pin "1") (pinfunction "1_1") (pintype "passive"))
      (node (ref "U14") (pin "M2") (pinfunction "PC14-OSC32_IN_M2") (pintype "passive"))
      (node (ref "X2") (pin "2") (pinfunction "X2_2") (pintype "passive"))
    )
    (net (code "175") (name "Net-(U14A-PC15-OSC32_OUT)") (class "Default")
      (node (ref "R103") (pin "1") (pinfunction "1_1") (pintype "passive"))
      (node (ref "U14") (pin "L3") (pinfunction "PC15-OSC32_OUT_L3") (pintype "passive"))
    )
    (net (code "176") (name "Net-(U14A-PD13)") (class "Default")
      (node (ref "R96") (pin "1") (pinfunction "1_1") (pintype "passive"))
      (node (ref "U14") (pin "J2") (pinfunction "PD13_J2") (pintype "passive"))
    )
    (net (code "177") (name "Net-(U14B-PE10)") (class "Default")
      (node (ref "R64") (pin "2") (pinfunction "2_2") (pintype "passive"))
      (node (ref "U14") (pin "C10") (pinfunction "PE10_C10") (pintype "passive"))
    )
    (net (code "178") (name "Net-(U14B-PF9)") (class "Default")
      (node (ref "R85") (pin "2") (pinfunction "2_2") (pintype "passive"))
      (node (ref "U14") (pin "J5") (pinfunction "PF9_J5") (pintype "passive"))
    )
    (net (code "179") (name "Net-(U14B-PWR_CPU_ON)") (class "Default")
      (node (ref "TP57") (pin "1") (pinfunction "1_1") (pintype "passive"))
      (node (ref "U14") (pin "W3") (pinfunction "PWR_CPU_ON_W3") (pintype "passive"))
    )
    (net (code "180") (name "Net-(U14C-USB_RREF)") (class "Default")
      (node (ref "R128") (pin "1") (pinfunction "1_1") (pintype "passive"))
      (node (ref "U14") (pin "W12") (pinfunction "USB_RREF_W12") (pintype "passive"))
    )
    (net (code "181") (name "Net-(X2-X1)") (class "Default")
      (node (ref "C88") (pin "1") (pinfunction "1_1") (pintype "passive"))
      (node (ref "R103") (pin "2") (pinfunction "2_2") (pintype "passive"))
      (node (ref "X2") (pin "1") (pinfunction "X1_1") (pintype "passive"))
    )
    (net (code "182") (name "VDD") (class "Default")
      (node (ref "R108") (pin "2") (pinfunction "2_2") (pintype "passive"))
      (node (ref "R62") (pin "2") (pinfunction "2_2") (pintype "passive"))
      (node (ref "R63") (pin "2") (pinfunction "2_2") (pintype "passive"))
      (node (ref "R71") (pin "2") (pinfunction "2_2") (pintype "passive"))
      (node (ref "R72") (pin "2") (pinfunction "2_2") (pintype "passive"))
      (node (ref "R75") (pin "2") (pinfunction "2_2") (pintype "passive"))
      (node (ref "R82") (pin "2") (pinfunction "2_2") (pintype "passive"))
      (node (ref "U14") (pin "AA12") (pinfunction "PDR_ON_AA12") (pintype "passive"))
    )
  )
)
